# MS5541-CM_Board.net
KiCad netlist of a schematic drawn in EAGLE
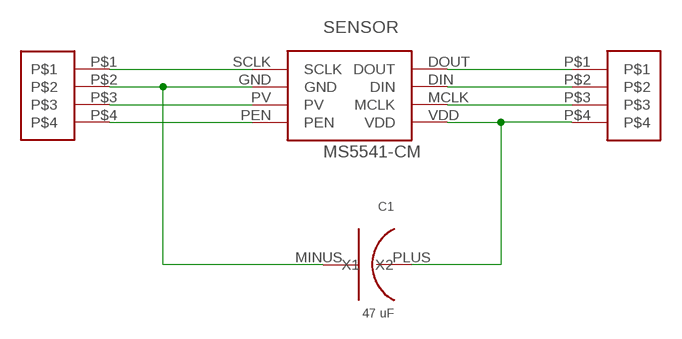
[diagram p0: schematic, sheet 1]

(export (version "E")
  (design (tool "Eeschema 10.0.6"))
  (components
    (comp (ref "C1")
      (value "47 uF")
      (footprint "eagle-import:C_SMD_TA_B_BOTTOM")
      (libsource (lib "eagle-import") (part "C_SMD_TA_B_BOTTOM"))
    )
    (comp (ref "SENSOR")
      (value "MS5541-CM")
      (footprint "eagle-import:MS5541-CM")
      (libsource (lib "eagle-import") (part "MS5541-CM"))
    )
    (comp (ref "U$3")
      (value "4-PIN-NONAME")
      (footprint "eagle-import:4-PIN-NONAME")
      (libsource (lib "eagle-import") (part "4-PIN-NONAME"))
    )
    (comp (ref "U$4")
      (value "4-PIN-NONAME")
      (footprint "eagle-import:4-PIN-NONAME")
      (libsource (lib "eagle-import") (part "4-PIN-NONAME"))
    )
  )
  (nets
    (net (code "1") (name "Net-(C1-X1)") (class "Default")
      (node (ref "C1") (pin "PLUS") (pinfunction "X1_PLUS") (pintype "bidirectional"))
      (node (ref "SENSOR") (pin "VDD") (pinfunction "VDD_VDD") (pintype "bidirectional"))
      (node (ref "U$3") (pin "P$4") (pinfunction "P$4_P$4") (pintype "bidirectional"))
    )
    (net (code "2") (name "Net-(C1-X2)") (class "Default")
      (node (ref "C1") (pin "MINUS") (pinfunction "X2_MINUS") (pintype "bidirectional"))
      (node (ref "SENSOR") (pin "GND") (pinfunction "GND_GND") (pintype "bidirectional"))
      (node (ref "U$4") (pin "P$2") (pinfunction "P$2_P$2") (pintype "bidirectional"))
    )
    (net (code "3") (name "Net-(SENSOR-PadDIN)") (class "Default")
      (node (ref "SENSOR") (pin "DIN") (pinfunction "DIN_DIN") (pintype "bidirectional"))
      (node (ref "U$3") (pin "P$2") (pinfunction "P$2_P$2") (pintype "bidirectional"))
    )
    (net (code "4") (name "Net-(SENSOR-PadDOUT)") (class "Default")
      (node (ref "SENSOR") (pin "DOUT") (pinfunction "DOUT_DOUT") (pintype "bidirectional"))
      (node (ref "U$3") (pin "P$1") (pinfunction "P$1_P$1") (pintype "bidirectional"))
    )
    (net (code "5") (name "Net-(SENSOR-PadMCLK)") (class "Default")
      (node (ref "SENSOR") (pin "MCLK") (pinfunction "MCLK_MCLK") (pintype "bidirectional"))
      (node (ref "U$3") (pin "P$3") (pinfunction "P$3_P$3") (pintype "bidirectional"))
    )
    (net (code "6") (name "Net-(SENSOR-PadPEN)") (class "Default")
      (node (ref "SENSOR") (pin "PEN") (pinfunction "PEN_PEN") (pintype "bidirectional"))
      (node (ref "U$4") (pin "P$4") (pinfunction "P$4_P$4") (pintype "bidirectional"))
    )
    (net (code "7") (name "Net-(SENSOR-PadPV)") (class "Default")
      (node (ref "SENSOR") (pin "PV") (pinfunction "PV_PV") (pintype "bidirectional"))
      (node (ref "U$4") (pin "P$3") (pinfunction "P$3_P$3") (pintype "bidirectional"))
    )
    (net (code "8") (name "Net-(SENSOR-PadSCLK)") (class "Default")
      (node (ref "SENSOR") (pin "SCLK") (pinfunction "SCLK_SCLK") (pintype "bidirectional"))
      (node (ref "U$4") (pin "P$1") (pinfunction "P$1_P$1") (pintype "bidirectional"))
    )
  )
)
